# MCU.net
KiCad netlist of a schematic drawn in Altium Designer
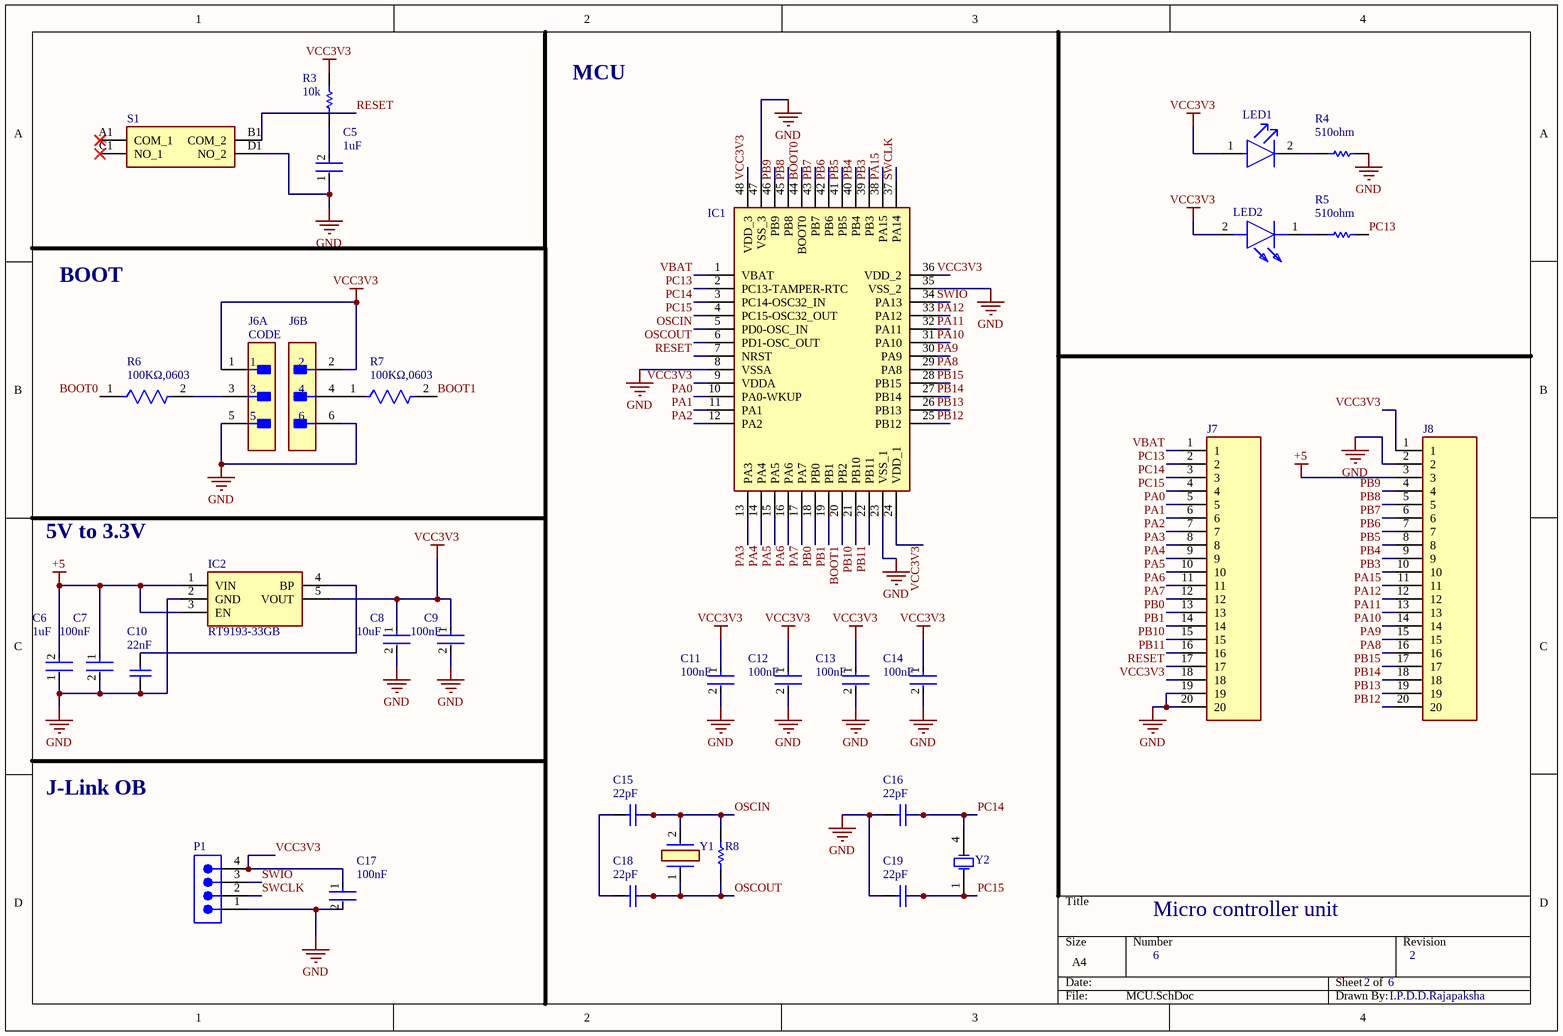
[diagram p0: MCU.SchDoc]

(export (version "E")
  (design (tool "Eeschema 10.0.6"))
  (components
    (comp (ref "C5")
      (value "C1608X6S1H105K080AC")
      (footprint "FP-C1608-080-0_1-IPC_A")
      (description "Multilayer Ceramic Capacitors 1μF ±10% 50V X6S SMD 0603")
      (fields (field (name "CAPACITANCE") "1uF") (field (name "TOLERANCE") "10%"))
      (libsource (lib "Altium Content Vault") (part "236180d848d6139a670b325ea6854c9"))
    )
    (comp (ref "C6")
      (value "C1608X6S1H105K080AC")
      (footprint "FP-C1608-080-0_1-IPC_A")
      (description "Multilayer Ceramic Capacitors 1μF ±10% 50V X6S SMD 0603")
      (fields (field (name "CAPACITANCE") "1uF") (field (name "TOLERANCE") "10%"))
      (libsource (lib "Altium Content Vault") (part "236180d848d6139a670b325ea6854c9"))
    )
    (comp (ref "C7")
      (value "C0603X5R1E104K030BB")
      (footprint "FP-C0603-030-0_03-IPC_C")
      (description "Multilayer Ceramic Capacitors 100nF ±10% 25V X5R SMD 0201")
      (fields (field (name "TOLERANCE") "10%") (field (name "CAPACITANCE") "100nF"))
      (libsource (lib "Altium Content Vault") (part "02cd4be3c70576c341d710602a673aa"))
    )
    (comp (ref "C8")
      (value "10uF")
      (footprint "FP-CL05A106MP5NUNC-MFG")
      (description "CAP CER 10UF 10V X5R 0402")
      (fields
        (field (name "OCTOPART") "https://octopart.com/cl05a106mp5nunc-samsung-22457395")
        (field (name "TOLERANCE") "20%")
      )
      (libsource (lib "Altium Content Vault") (part "b4654b650e69147ec39a6b967a45e02"))
    )
    (comp (ref "C9")
      (value "C0603X5R1E104K030BB")
      (footprint "FP-C0603-030-0_03-IPC_C")
      (description "Multilayer Ceramic Capacitors 100nF ±10% 25V X5R SMD 0201")
      (fields (field (name "TOLERANCE") "10%") (field (name "CAPACITANCE") "100nF"))
      (libsource (lib "Altium Content Vault") (part "02cd4be3c70576c341d710602a673aa"))
    )
    (comp (ref "C10")
      (value "C0603S223K5RACTU")
      (footprint "CAPC1608X87X35ML15T15")
      (fields (field (name "MANUFACTURER") "Kemet") (field (name "PARAMETER 1") "22nF"))
      (libsource (lib "Altium Content Vault") (part "CAP"))
    )
    (comp (ref "C11")
      (value "C0603X5R1E104K030BB")
      (footprint "FP-C0603-030-0_03-IPC_C")
      (description "Multilayer Ceramic Capacitors 100nF ±10% 25V X5R SMD 0201")
      (fields (field (name "TOLERANCE") "10%") (field (name "CAPACITANCE") "100nF"))
      (libsource (lib "Altium Content Vault") (part "02cd4be3c70576c341d710602a673aa"))
    )
    (comp (ref "C12")
      (value "C0603X5R1E104K030BB")
      (footprint "FP-C0603-030-0_03-IPC_C")
      (description "Multilayer Ceramic Capacitors 100nF ±10% 25V X5R SMD 0201")
      (fields (field (name "TOLERANCE") "10%") (field (name "CAPACITANCE") "100nF"))
      (libsource (lib "Altium Content Vault") (part "02cd4be3c70576c341d710602a673aa"))
    )
    (comp (ref "C13")
      (value "C0603X5R1E104K030BB")
      (footprint "FP-C0603-030-0_03-IPC_C")
      (description "Multilayer Ceramic Capacitors 100nF ±10% 25V X5R SMD 0201")
      (fields (field (name "TOLERANCE") "10%") (field (name "CAPACITANCE") "100nF"))
      (libsource (lib "Altium Content Vault") (part "02cd4be3c70576c341d710602a673aa"))
    )
    (comp (ref "C14")
      (value "C0603X5R1E104K030BB")
      (footprint "FP-C0603-030-0_03-IPC_C")
      (description "Multilayer Ceramic Capacitors 100nF ±10% 25V X5R SMD 0201")
      (fields (field (name "TOLERANCE") "10%") (field (name "CAPACITANCE") "100nF"))
      (libsource (lib "Altium Content Vault") (part "02cd4be3c70576c341d710602a673aa"))
    )
    (comp (ref "C15")
      (value "CC0402JRNPO9BN220")
      (footprint "CAPC1005X55X25ML05T05")
      (description "Chip Capacitor, 22 pF, +/- 5%, 50 V, -55 to 125 degC, 0402 (1005 Metric), RoHS, Tape and Reel")
      (fields
        (field (name "CAPACITANCE") "22pF")
        (field (name "MANUFACTURER") "Yageo")
        (field (name "TOLERANCE") "5%")
      )
      (libsource (lib "Altium Content Vault") (part "CAP-NP-2"))
    )
    (comp (ref "C16")
      (value "CC0402JRNPO9BN220")
      (footprint "CAPC1005X55X25ML05T05")
      (description "Chip Capacitor, 22 pF, +/- 5%, 50 V, -55 to 125 degC, 0402 (1005 Metric), RoHS, Tape and Reel")
      (fields
        (field (name "CAPACITANCE") "22pF")
        (field (name "MANUFACTURER") "Yageo")
        (field (name "TOLERANCE") "5%")
      )
      (libsource (lib "Altium Content Vault") (part "CAP-NP-2"))
    )
    (comp (ref "C17")
      (value "C0603X5R1E104K030BB")
      (footprint "FP-C0603-030-0_03-IPC_C")
      (description "Multilayer Ceramic Capacitors 100nF ±10% 25V X5R SMD 0201")
      (fields (field (name "TOLERANCE") "10%") (field (name "CAPACITANCE") "100nF"))
      (libsource (lib "Altium Content Vault") (part "02cd4be3c70576c341d710602a673aa"))
    )
    (comp (ref "C18")
      (value "CC0402JRNPO9BN220")
      (footprint "CAPC1005X55X25ML05T05")
      (description "Chip Capacitor, 22 pF, +/- 5%, 50 V, -55 to 125 degC, 0402 (1005 Metric), RoHS, Tape and Reel")
      (fields
        (field (name "CAPACITANCE") "22pF")
        (field (name "MANUFACTURER") "Yageo")
        (field (name "TOLERANCE") "5%")
      )
      (libsource (lib "Altium Content Vault") (part "CAP-NP-2"))
    )
    (comp (ref "C19")
      (value "CC0402JRNPO9BN220")
      (footprint "CAPC1005X55X25ML05T05")
      (description "Chip Capacitor, 22 pF, +/- 5%, 50 V, -55 to 125 degC, 0402 (1005 Metric), RoHS, Tape and Reel")
      (fields
        (field (name "CAPACITANCE") "22pF")
        (field (name "MANUFACTURER") "Yageo")
        (field (name "TOLERANCE") "5%")
      )
      (libsource (lib "Altium Content Vault") (part "CAP-NP-2"))
    )
    (comp (ref "IC1")
      (value "STM32F103C8T6XXX")
      (footprint "SamacSys:QFP50P900X900X160-48N")
      (description "Integrated Circuit")
      (libsource (lib "*") (part "STM32F103C8T6XXX"))
    )
    (comp (ref "IC2")
      (value "RT9193-33GB")
      (footprint "SamacSys:SOT94P279X130-5N")
      (description "Integrated Circuit")
      (fields (field (name "MOUSER PART NUMBER") "835-RT9193-33GB"))
      (libsource (lib "*") (part "RT9193-33GB"))
    )
    (comp (ref "J6")
      (value "90131-0763")
      (footprint "FP-90131-0763-MFG")
      (description "90131-0763 Conn Unshrouded Header HDR 6 POS 2.54mm Solder ST Top Entry Thru-Hole C-Grid III™ Tray")
      (fields (field (name "PARAMETER 1") "CODE"))
      (libsource (lib "Altium Content Vault") (part "2654a11fb13586ecb194516b1c997bc"))
    )
    (comp (ref "J7")
      (value "TS-120-G-A-1")
      (footprint "SamacSys:HDRV20W64P0X254_1X20_5080X254X808P")
      (description "Connector")
      (fields (field (name "MOUSER PART NUMBER") "200-TS120GA1"))
      (libsource (lib "*") (part "TS-120-G-A-1"))
    )
    (comp (ref "J8")
      (value "TS-120-G-A-1")
      (footprint "SamacSys:HDRV20W64P0X254_1X20_5080X254X808P")
      (description "Connector")
      (fields (field (name "MOUSER PART NUMBER") "200-TS120GA1"))
      (libsource (lib "*") (part "TS-120-G-A-1"))
    )
    (comp (ref "LED1")
      (value "SM0805UBWC")
      (footprint "FP-SM0805UBWC-MFG")
      (description "LED BLUE CLEAR 0805 SMD")
      (libsource (lib "Altium Content Vault") (part "ab1c01a81903e929fc6c44469aada92"))
    )
    (comp (ref "LED2")
      (value "SM0805RC")
      (footprint "SamacSys:LEDC2012X110N")
      (description "LED")
      (fields (field (name "MOUSER PART NUMBER") "749-SM0805RC"))
      (libsource (lib "*") (part "SM0805RC"))
    )
    (comp (ref "P1")
      (value "61300411021")
      (footprint "61300411021")
      (libsource (lib "Altium Content Vault") (part "Header_Male_1R_04P"))
    )
    (comp (ref "R3")
      (value "CPF0402B30KE1")
      (footprint "RESC1005X35X20ML05T10")
      (fields (field (name "MANUFACTURER") "TE Connectivity / AMP") (field (name "PARAMETER 1") "10k"))
      (libsource (lib "Altium Content Vault") (part "RES"))
    )
    (comp (ref "R4")
      (value "CRCW0603510RFKEA")
      (footprint "RESC1609X50X30NL10T20")
      (fields (field (name "MANUFACTURER") "Vishay Dale") (field (name "PARAMETER 1") "510ohm"))
      (libsource (lib "Altium Content Vault") (part "RES"))
    )
    (comp (ref "R5")
      (value "CRCW0603510RFKEA")
      (footprint "RESC1609X50X30NL10T20")
      (fields (field (name "MANUFACTURER") "Vishay Dale") (field (name "PARAMETER 1") "510ohm"))
      (libsource (lib "Altium Content Vault") (part "RES"))
    )
    (comp (ref "R6")
      (value "100KΩ,0603")
      (footprint "FP-SR0603-MFG")
      (description "RES SMD 0603 1/4W 1% 100K OHM")
      (fields
        (field (name "OCTOPART") "https://octopart.com/sr0603fr-7t100kl-yageo-91478071")
        (field (name "TOLERANCE") "0.01")
      )
      (libsource (lib "Altium Content Vault") (part "1029c3af85768c4190bb7ad29bc67b5"))
    )
    (comp (ref "R7")
      (value "100KΩ,0603")
      (footprint "FP-SR0603-MFG")
      (description "RES SMD 0603 1/4W 1% 100K OHM")
      (fields
        (field (name "OCTOPART") "https://octopart.com/sr0603fr-7t100kl-yageo-91478071")
        (field (name "TOLERANCE") "0.01")
      )
      (libsource (lib "Altium Content Vault") (part "1029c3af85768c4190bb7ad29bc67b5"))
    )
    (comp (ref "R8")
      (value "RK73B2ATTD105J")
      (footprint "RESC2013X60X30NL20T20")
      (fields (field (name "MANUFACTURER") "KOA Speer"))
      (libsource (lib "Altium Content Vault") (part "RES"))
    )
    (comp (ref "S1")
      (value "TS-1187A-B-A-B")
      (footprint "SamacSys:TS1187ABAB")
      (description "Switch")
      (libsource (lib "*") (part "TS-1187A-B-A-B"))
    )
    (comp (ref "Y1")
      (value "XT9S20ANA8M")
      (footprint "SamacSys:XT9S20ANA8M")
      (description "Crystal or Oscillator")
      (fields (field (name "MOUSER PART NUMBER") "73-XT49S800-20"))
      (libsource (lib "*") (part "XT9S20ANA8M"))
    )
    (comp (ref "Y2")
      (value "830003000")
      (footprint "WE-XTAL_85SMX")
      (description "830003000 WE-XTAL Quartz Crystal")
      (libsource (lib "Altium Content Vault") (part "WE-XTAL_85SMX"))
    )
  )
  (nets
    (net (code "1") (name "+5") (class "Default")
      (node (ref "C6") (pin "2") (pinfunction "2_2") (pintype "passive"))
      (node (ref "C7") (pin "1") (pinfunction "1_1") (pintype "passive"))
      (node (ref "IC2") (pin "1") (pinfunction "VIN_1") (pintype "passive"))
      (node (ref "IC2") (pin "3") (pinfunction "EN_3") (pintype "passive"))
      (node (ref "J8") (pin "3") (pinfunction "3_3") (pintype "passive"))
    )
    (net (code "2") (name "/BOOT0") (class "Default")
      (node (ref "IC1") (pin "44") (pinfunction "BOOT0_44") (pintype "passive"))
      (node (ref "R6") (pin "1") (pinfunction "1_1") (pintype "passive"))
    )
    (net (code "3") (name "/BOOT1") (class "Default")
      (node (ref "IC1") (pin "20") (pinfunction "PB2_20") (pintype "passive"))
      (node (ref "R7") (pin "2") (pinfunction "2_2") (pintype "passive"))
    )
    (net (code "4") (name "/OSCIN") (class "Default")
      (node (ref "C15") (pin "2") (pinfunction "2_2") (pintype "passive"))
      (node (ref "IC1") (pin "5") (pinfunction "PD0-OSC_IN_5") (pintype "passive"))
      (node (ref "R8") (pin "2") (pinfunction "2_2") (pintype "passive"))
      (node (ref "Y1") (pin "2") (pinfunction "2_2") (pintype "passive"))
    )
    (net (code "5") (name "/OSCOUT") (class "Default")
      (node (ref "C18") (pin "2") (pinfunction "2_2") (pintype "passive"))
      (node (ref "IC1") (pin "6") (pinfunction "PD1-OSC_OUT_6") (pintype "passive"))
      (node (ref "R8") (pin "1") (pinfunction "1_1") (pintype "passive"))
      (node (ref "Y1") (pin "1") (pinfunction "1_1") (pintype "passive"))
    )
    (net (code "6") (name "/PA0") (class "Default")
      (node (ref "IC1") (pin "10") (pinfunction "PA0-WKUP_10") (pintype "passive"))
      (node (ref "J7") (pin "5") (pinfunction "5_5") (pintype "passive"))
    )
    (net (code "7") (name "/PA1") (class "Default")
      (node (ref "IC1") (pin "11") (pinfunction "PA1_11") (pintype "passive"))
      (node (ref "J7") (pin "6") (pinfunction "6_6") (pintype "passive"))
    )
    (net (code "8") (name "/PA2") (class "Default")
      (node (ref "IC1") (pin "12") (pinfunction "PA2_12") (pintype "passive"))
      (node (ref "J7") (pin "7") (pinfunction "7_7") (pintype "passive"))
    )
    (net (code "9") (name "/PA3") (class "Default")
      (node (ref "IC1") (pin "13") (pinfunction "PA3_13") (pintype "passive"))
      (node (ref "J7") (pin "8") (pinfunction "8_8") (pintype "passive"))
    )
    (net (code "10") (name "/PA4") (class "Default")
      (node (ref "IC1") (pin "14") (pinfunction "PA4_14") (pintype "passive"))
      (node (ref "J7") (pin "9") (pinfunction "9_9") (pintype "passive"))
    )
    (net (code "11") (name "/PA5") (class "Default")
      (node (ref "IC1") (pin "15") (pinfunction "PA5_15") (pintype "passive"))
      (node (ref "J7") (pin "10") (pinfunction "10_10") (pintype "passive"))
    )
    (net (code "12") (name "/PA6") (class "Default")
      (node (ref "IC1") (pin "16") (pinfunction "PA6_16") (pintype "passive"))
      (node (ref "J7") (pin "11") (pinfunction "11_11") (pintype "passive"))
    )
    (net (code "13") (name "/PA7") (class "Default")
      (node (ref "IC1") (pin "17") (pinfunction "PA7_17") (pintype "passive"))
      (node (ref "J7") (pin "12") (pinfunction "12_12") (pintype "passive"))
    )
    (net (code "14") (name "/PA8") (class "Default")
      (node (ref "IC1") (pin "29") (pinfunction "PA8_29") (pintype "passive"))
      (node (ref "J8") (pin "16") (pinfunction "16_16") (pintype "passive"))
    )
    (net (code "15") (name "/PA9") (class "Default")
      (node (ref "IC1") (pin "30") (pinfunction "PA9_30") (pintype "passive"))
      (node (ref "J8") (pin "15") (pinfunction "15_15") (pintype "passive"))
    )
    (net (code "16") (name "/PA10") (class "Default")
      (node (ref "IC1") (pin "31") (pinfunction "PA10_31") (pintype "passive"))
      (node (ref "J8") (pin "14") (pinfunction "14_14") (pintype "passive"))
    )
    (net (code "17") (name "/PA11") (class "Default")
      (node (ref "IC1") (pin "32") (pinfunction "PA11_32") (pintype "passive"))
      (node (ref "J8") (pin "13") (pinfunction "13_13") (pintype "passive"))
    )
    (net (code "18") (name "/PA12") (class "Default")
      (node (ref "IC1") (pin "33") (pinfunction "PA12_33") (pintype "passive"))
      (node (ref "J8") (pin "12") (pinfunction "12_12") (pintype "passive"))
    )
    (net (code "19") (name "/PA15") (class "Default")
      (node (ref "IC1") (pin "38") (pinfunction "PA15_38") (pintype "passive"))
      (node (ref "J8") (pin "11") (pinfunction "11_11") (pintype "passive"))
    )
    (net (code "20") (name "/PB0") (class "Default")
      (node (ref "IC1") (pin "18") (pinfunction "PB0_18") (pintype "passive"))
      (node (ref "J7") (pin "13") (pinfunction "13_13") (pintype "passive"))
    )
    (net (code "21") (name "/PB1") (class "Default")
      (node (ref "IC1") (pin "19") (pinfunction "PB1_19") (pintype "passive"))
      (node (ref "J7") (pin "14") (pinfunction "14_14") (pintype "passive"))
    )
    (net (code "22") (name "/PB3") (class "Default")
      (node (ref "IC1") (pin "39") (pinfunction "PB3_39") (pintype "passive"))
      (node (ref "J8") (pin "10") (pinfunction "10_10") (pintype "passive"))
    )
    (net (code "23") (name "/PB4") (class "Default")
      (node (ref "IC1") (pin "40") (pinfunction "PB4_40") (pintype "passive"))
      (node (ref "J8") (pin "9") (pinfunction "9_9") (pintype "passive"))
    )
    (net (code "24") (name "/PB5") (class "Default")
      (node (ref "IC1") (pin "41") (pinfunction "PB5_41") (pintype "passive"))
      (node (ref "J8") (pin "8") (pinfunction "8_8") (pintype "passive"))
    )
    (net (code "25") (name "/PB6") (class "Default")
      (node (ref "IC1") (pin "42") (pinfunction "PB6_42") (pintype "passive"))
      (node (ref "J8") (pin "7") (pinfunction "7_7") (pintype "passive"))
    )
    (net (code "26") (name "/PB7") (class "Default")
      (node (ref "IC1") (pin "43") (pinfunction "PB7_43") (pintype "passive"))
      (node (ref "J8") (pin "6") (pinfunction "6_6") (pintype "passive"))
    )
    (net (code "27") (name "/PB8") (class "Default")
      (node (ref "IC1") (pin "45") (pinfunction "PB8_45") (pintype "passive"))
      (node (ref "J8") (pin "5") (pinfunction "5_5") (pintype "passive"))
    )
    (net (code "28") (name "/PB9") (class "Default")
      (node (ref "IC1") (pin "46") (pinfunction "PB9_46") (pintype "passive"))
      (node (ref "J8") (pin "4") (pinfunction "4_4") (pintype "passive"))
    )
    (net (code "29") (name "/PB10") (class "Default")
      (node (ref "IC1") (pin "21") (pinfunction "PB10_21") (pintype "passive"))
      (node (ref "J7") (pin "15") (pinfunction "15_15") (pintype "passive"))
    )
    (net (code "30") (name "/PB11") (class "Default")
      (node (ref "IC1") (pin "22") (pinfunction "PB11_22") (pintype "passive"))
      (node (ref "J7") (pin "16") (pinfunction "16_16") (pintype "passive"))
    )
    (net (code "31") (name "/PB12") (class "Default")
      (node (ref "IC1") (pin "25") (pinfunction "PB12_25") (pintype "passive"))
      (node (ref "J8") (pin "20") (pinfunction "20_20") (pintype "passive"))
    )
    (net (code "32") (name "/PB13") (class "Default")
      (node (ref "IC1") (pin "26") (pinfunction "PB13_26") (pintype "passive"))
      (node (ref "J8") (pin "19") (pinfunction "19_19") (pintype "passive"))
    )
    (net (code "33") (name "/PB14") (class "Default")
      (node (ref "IC1") (pin "27") (pinfunction "PB14_27") (pintype "passive"))
      (node (ref "J8") (pin "18") (pinfunction "18_18") (pintype "passive"))
    )
    (net (code "34") (name "/PB15") (class "Default")
      (node (ref "IC1") (pin "28") (pinfunction "PB15_28") (pintype "passive"))
      (node (ref "J8") (pin "17") (pinfunction "17_17") (pintype "passive"))
    )
    (net (code "35") (name "/PC13") (class "Default")
      (node (ref "IC1") (pin "2") (pinfunction "PC13-TAMPER-RTC_2") (pintype "passive"))
      (node (ref "J7") (pin "2") (pinfunction "2_2") (pintype "passive"))
      (node (ref "R5") (pin "2") (pinfunction "2_2") (pintype "passive"))
    )
    (net (code "36") (name "/PC14") (class "Default")
      (node (ref "C16") (pin "2") (pinfunction "2_2") (pintype "passive"))
      (node (ref "IC1") (pin "3") (pinfunction "PC14-OSC32_IN_3") (pintype "passive"))
      (node (ref "J7") (pin "3") (pinfunction "3_3") (pintype "passive"))
      (node (ref "Y2") (pin "4") (pinfunction "Crystal_4") (pintype "passive"))
    )
    (net (code "37") (name "/PC15") (class "Default")
      (node (ref "C19") (pin "2") (pinfunction "2_2") (pintype "passive"))
      (node (ref "IC1") (pin "4") (pinfunction "PC15-OSC32_OUT_4") (pintype "passive"))
      (node (ref "J7") (pin "4") (pinfunction "4_4") (pintype "passive"))
      (node (ref "Y2") (pin "1") (pinfunction "Crystal_1") (pintype "passive"))
    )
    (net (code "38") (name "/RESET") (class "Default")
      (node (ref "IC1") (pin "7") (pinfunction "NRST_7") (pintype "passive"))
      (node (ref "J7") (pin "17") (pinfunction "17_17") (pintype "passive"))
      (node (ref "S1") (pin "B1") (pinfunction "COM_2_B1") (pintype "passive"))
    )
    (net (code "39") (name "/SWCLK") (class "Default")
      (node (ref "IC1") (pin "37") (pinfunction "PA14_37") (pintype "passive"))
      (node (ref "P1") (pin "2") (pinfunction "2_2") (pintype "passive"))
    )
    (net (code "40") (name "/SWIO") (class "Default")
      (node (ref "IC1") (pin "34") (pinfunction "PA13_34") (pintype "passive"))
      (node (ref "P1") (pin "3") (pinfunction "3_3") (pintype "passive"))
    )
    (net (code "41") (name "/VBAT") (class "Default")
      (node (ref "IC1") (pin "1") (pinfunction "VBAT_1") (pintype "passive"))
      (node (ref "J7") (pin "1") (pinfunction "1_1") (pintype "passive"))
    )
    (net (code "42") (name "GND") (class "Default")
      (node (ref "C10") (pin "1") (pinfunction "1_1") (pintype "passive"))
      (node (ref "C11") (pin "2") (pinfunction "2_2") (pintype "passive"))
      (node (ref "C12") (pin "2") (pinfunction "2_2") (pintype "passive"))
      (node (ref "C13") (pin "2") (pinfunction "2_2") (pintype "passive"))
      (node (ref "C14") (pin "2") (pinfunction "2_2") (pintype "passive"))
      (node (ref "C16") (pin "1") (pinfunction "1_1") (pintype "passive"))
      (node (ref "C17") (pin "2") (pinfunction "2_2") (pintype "passive"))
      (node (ref "C19") (pin "1") (pinfunction "1_1") (pintype "passive"))
      (node (ref "C5") (pin "1") (pinfunction "1_1") (pintype "passive"))
      (node (ref "C6") (pin "1") (pinfunction "1_1") (pintype "passive"))
      (node (ref "C7") (pin "2") (pinfunction "2_2") (pintype "passive"))
      (node (ref "C8") (pin "2") (pinfunction "2_2") (pintype "passive"))
      (node (ref "C9") (pin "2") (pinfunction "2_2") (pintype "passive"))
      (node (ref "IC1") (pin "23") (pinfunction "VSS_1_23") (pintype "passive"))
      (node (ref "IC1") (pin "35") (pinfunction "VSS_2_35") (pintype "passive"))
      (node (ref "IC1") (pin "47") (pinfunction "VSS_3_47") (pintype "passive"))
      (node (ref "IC1") (pin "8") (pinfunction "VSSA_8") (pintype "passive"))
      (node (ref "IC2") (pin "2") (pinfunction "GND_2") (pintype "passive"))
      (node (ref "J6") (pin "5") (pinfunction "5_5") (pintype "passive"))
      (node (ref "J6") (pin "6") (pinfunction "6_6") (pintype "passive"))
      (node (ref "J7") (pin "19") (pinfunction "19_19") (pintype "passive"))
      (node (ref "J7") (pin "20") (pinfunction "20_20") (pintype "passive"))
      (node (ref "J8") (pin "2") (pinfunction "2_2") (pintype "passive"))
      (node (ref "P1") (pin "1") (pinfunction "1_1") (pintype "passive"))
      (node (ref "R4") (pin "2") (pinfunction "2_2") (pintype "passive"))
      (node (ref "S1") (pin "D1") (pinfunction "NO_2_D1") (pintype "passive"))
    )
    (net (code "43") (name "Net-(C5-Pad2)") (class "Default")
      (node (ref "C5") (pin "2") (pinfunction "2_2") (pintype "passive"))
      (node (ref "R3") (pin "1") (pinfunction "1_1") (pintype "passive"))
    )
    (net (code "44") (name "Net-(C15-Pad1)") (class "Default")
      (node (ref "C15") (pin "1") (pinfunction "1_1") (pintype "passive"))
      (node (ref "C18") (pin "1") (pinfunction "1_1") (pintype "passive"))
    )
    (net (code "45") (name "Net-(IC2-BP)") (class "Default")
      (node (ref "C10") (pin "2") (pinfunction "2_2") (pintype "passive"))
      (node (ref "IC2") (pin "4") (pinfunction "BP_4") (pintype "passive"))
    )
    (net (code "46") (name "Net-(J6-Pad3)") (class "Default")
      (node (ref "J6") (pin "3") (pinfunction "3_3") (pintype "passive"))
      (node (ref "R6") (pin "2") (pinfunction "2_2") (pintype "passive"))
    )
    (net (code "47") (name "Net-(J6-Pad4)") (class "Default")
      (node (ref "J6") (pin "4") (pinfunction "4_4") (pintype "passive"))
      (node (ref "R7") (pin "1") (pinfunction "1_1") (pintype "passive"))
    )
    (net (code "48") (name "Net-(LED1-C)") (class "Default")
      (node (ref "LED1") (pin "2") (pinfunction "C_2") (pintype "passive"))
      (node (ref "R4") (pin "1") (pinfunction "1_1") (pintype "passive"))
    )
    (net (code "49") (name "Net-(LED2-K)") (class "Default")
      (node (ref "LED2") (pin "1") (pinfunction "K_1") (pintype "passive"))
      (node (ref "R5") (pin "1") (pinfunction "1_1") (pintype "passive"))
    )
    (net (code "50") (name "VCC3V3") (class "Default")
      (node (ref "C11") (pin "1") (pinfunction "1_1") (pintype "passive"))
      (node (ref "C12") (pin "1") (pinfunction "1_1") (pintype "passive"))
      (node (ref "C13") (pin "1") (pinfunction "1_1") (pintype "passive"))
      (node (ref "C14") (pin "1") (pinfunction "1_1") (pintype "passive"))
      (node (ref "C17") (pin "1") (pinfunction "1_1") (pintype "passive"))
      (node (ref "C8") (pin "1") (pinfunction "1_1") (pintype "passive"))
      (node (ref "C9") (pin "1") (pinfunction "1_1") (pintype "passive"))
      (node (ref "IC1") (pin "24") (pinfunction "VDD_1_24") (pintype "passive"))
      (node (ref "IC1") (pin "36") (pinfunction "VDD_2_36") (pintype "passive"))
      (node (ref "IC1") (pin "48") (pinfunction "VDD_3_48") (pintype "passive"))
      (node (ref "IC1") (pin "9") (pinfunction "VDDA_9") (pintype "passive"))
      (node (ref "IC2") (pin "5") (pinfunction "VOUT_5") (pintype "passive"))
      (node (ref "J6") (pin "1") (pinfunction "1_1") (pintype "passive"))
      (node (ref "J6") (pin "2") (pinfunction "2_2") (pintype "passive"))
      (node (ref "J7") (pin "18") (pinfunction "18_18") (pintype "passive"))
      (node (ref "J8") (pin "1") (pinfunction "1_1") (pintype "passive"))
      (node (ref "LED1") (pin "1") (pinfunction "A_1") (pintype "passive"))
      (node (ref "LED2") (pin "2") (pinfunction "A_2") (pintype "passive"))
      (node (ref "P1") (pin "4") (pinfunction "4_4") (pintype "passive"))
      (node (ref "R3") (pin "2") (pinfunction "2_2") (pintype "passive"))
    )
    (net (code "51") (name "unconnected-(S1-COM_1-PadA1)") (class "Default")
      (node (ref "S1") (pin "A1") (pinfunction "COM_1_A1") (pintype "passive+no_connect"))
    )
    (net (code "52") (name "unconnected-(S1-NO_1-PadC1)") (class "Default")
      (node (ref "S1") (pin "C1") (pinfunction "NO_1_C1") (pintype "passive+no_connect"))
    )
  )
)
